# 6_DIG.net
KiCad netlist of a schematic drawn in Altium Designer
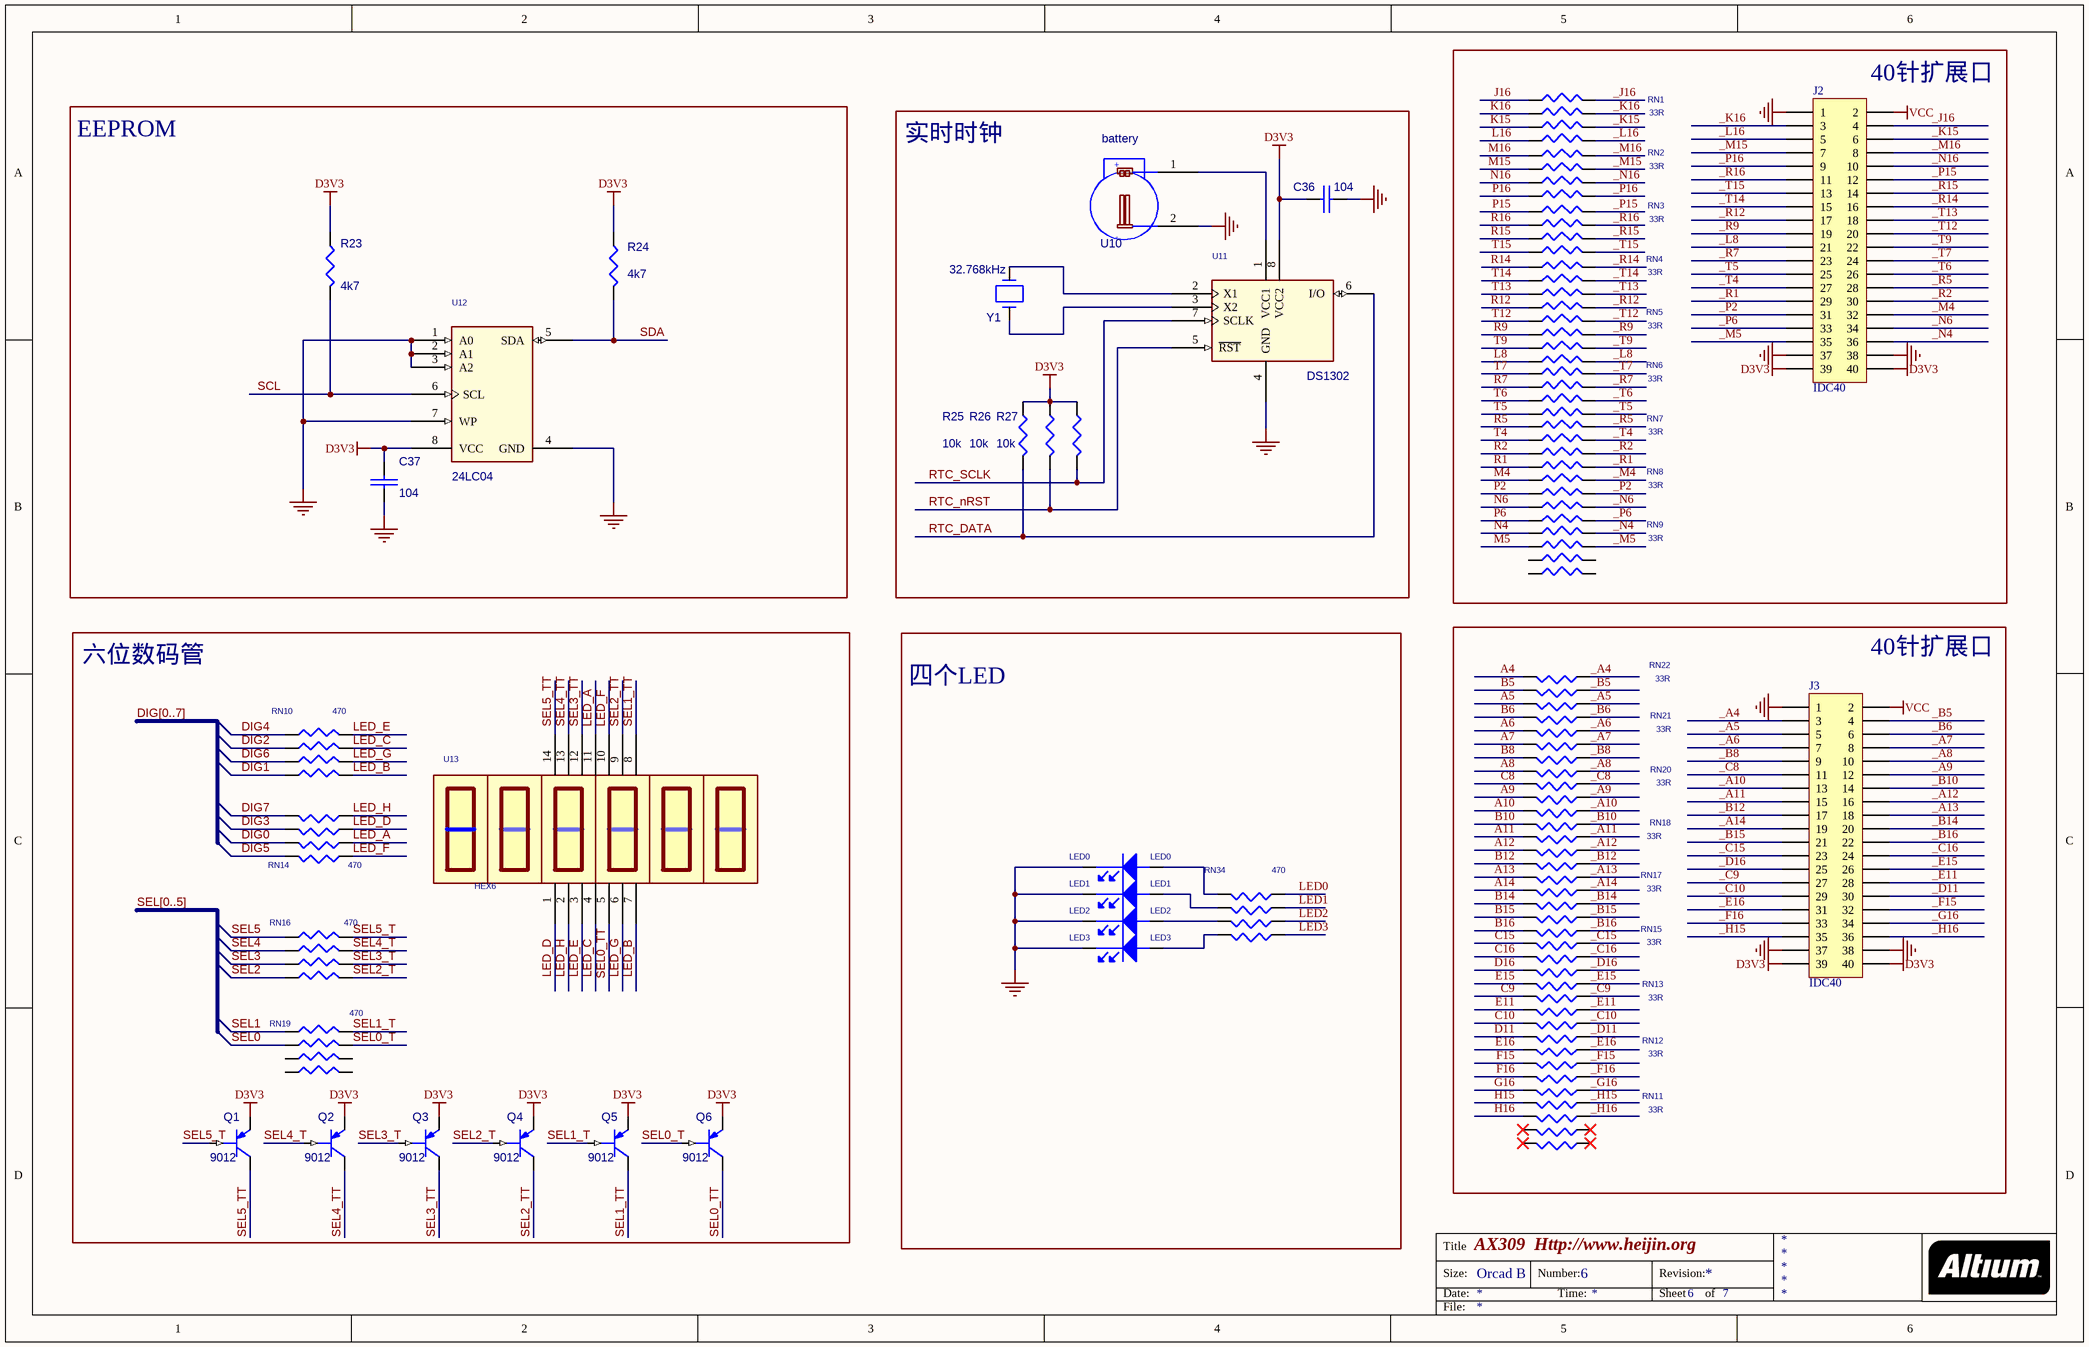
[diagram p0: 6_DIG.SchDoc]

(export (version "E")
  (design (tool "Eeschema 10.0.6"))
  (components
    (comp (ref "C36") (value "104") (footprint "0402") (libsource (lib "*") (part "C_Dup3")))
    (comp (ref "C37") (value "104") (footprint "0402") (libsource (lib "*") (part "C_Dup4")))
    (comp (ref "J2")
      (value "IDC40")
      (footprint "IDC-40J")
      (description "Header, 20-Pin, Dual row")
      (fields (field (name "PUBLISHER") "Altium Limited"))
      (libsource (lib "Miscellaneous Connectors") (part "MHDR2X20"))
    )
    (comp (ref "J3")
      (value "IDC40")
      (footprint "IDC-40J")
      (description "Header, 20-Pin, Dual row")
      (fields (field (name "PUBLISHER") "Altium Limited"))
      (libsource (lib "Miscellaneous Connectors") (part "MHDR2X20"))
    )
    (comp (ref "LED0") (value "LED0") (footprint "LEDSO") (libsource (lib "*") (part "LED_Dup1")))
    (comp (ref "LED1") (value "LED1") (footprint "LEDso") (libsource (lib "*") (part "LED_Dup1")))
    (comp (ref "LED2") (value "LED2") (footprint "LEDSO") (libsource (lib "*") (part "LED_Dup1")))
    (comp (ref "LED3") (value "LED3") (footprint "LEDSO") (libsource (lib "*") (part "LED_Dup1")))
    (comp (ref "Q1") (value "9012") (footprint "SOT23") (libsource (lib "*") (part "PNP")))
    (comp (ref "Q2") (value "9012") (footprint "SOT23") (libsource (lib "*") (part "PNP")))
    (comp (ref "Q3") (value "9012") (footprint "SOT23") (libsource (lib "*") (part "PNP")))
    (comp (ref "Q4") (value "9012") (footprint "SOT23") (libsource (lib "*") (part "PNP")))
    (comp (ref "Q5") (value "9012") (footprint "SOT23") (libsource (lib "*") (part "PNP")))
    (comp (ref "Q6") (value "9012") (footprint "SOT23") (libsource (lib "*") (part "PNP")))
    (comp (ref "R23") (value "4k7") (footprint "0603") (libsource (lib "*") (part "R_Dup6")))
    (comp (ref "R24") (value "4k7") (footprint "0603") (libsource (lib "*") (part "R_Dup6")))
    (comp (ref "R25") (value "10k") (footprint "0603") (libsource (lib "*") (part "R_Dup5")))
    (comp (ref "R26") (value "10k") (footprint "0603") (libsource (lib "*") (part "R_Dup5")))
    (comp (ref "R27") (value "10k") (footprint "0603") (libsource (lib "*") (part "R_Dup5")))
    (comp (ref "RN1") (value "33R") (footprint "RN-8P") (libsource (lib "*") (part "RN_Dup1")))
    (comp (ref "RN2") (value "33R") (footprint "RN-8P") (libsource (lib "*") (part "RN_Dup1")))
    (comp (ref "RN3") (value "33R") (footprint "RN-8P") (libsource (lib "*") (part "RN_Dup1")))
    (comp (ref "RN4") (value "33R") (footprint "RN-8P") (libsource (lib "*") (part "RN_Dup1")))
    (comp (ref "RN5") (value "33R") (footprint "RN-8P") (libsource (lib "*") (part "RN_Dup1")))
    (comp (ref "RN6") (value "33R") (footprint "RN-8P") (libsource (lib "*") (part "RN_Dup1")))
    (comp (ref "RN7") (value "33R") (footprint "RN-8P") (libsource (lib "*") (part "RN_Dup1")))
    (comp (ref "RN8") (value "33R") (footprint "RN-8P") (libsource (lib "*") (part "RN_Dup1")))
    (comp (ref "RN9") (value "33R") (footprint "RN-8P") (libsource (lib "*") (part "RN_Dup1")))
    (comp (ref "RN10") (value "470") (footprint "RN-8P") (libsource (lib "*") (part "RN")))
    (comp (ref "RN11") (value "33R") (footprint "RN-8P") (libsource (lib "*") (part "RN_Dup1")))
    (comp (ref "RN12") (value "33R") (footprint "RN-8P") (libsource (lib "*") (part "RN_Dup1")))
    (comp (ref "RN13") (value "33R") (footprint "RN-8P") (libsource (lib "*") (part "RN_Dup1")))
    (comp (ref "RN14") (value "470") (footprint "RN-8P") (libsource (lib "*") (part "RN")))
    (comp (ref "RN15") (value "33R") (footprint "RN-8P") (libsource (lib "*") (part "RN_Dup1")))
    (comp (ref "RN16") (value "470") (footprint "RN-8P") (libsource (lib "*") (part "RN")))
    (comp (ref "RN17") (value "33R") (footprint "RN-8P") (libsource (lib "*") (part "RN_Dup1")))
    (comp (ref "RN18") (value "33R") (footprint "RN-8P") (libsource (lib "*") (part "RN_Dup1")))
    (comp (ref "RN19") (value "470") (footprint "RN-8P") (libsource (lib "*") (part "RN")))
    (comp (ref "RN20") (value "33R") (footprint "RN-8P") (libsource (lib "*") (part "RN_Dup1")))
    (comp (ref "RN21") (value "33R") (footprint "RN-8P") (libsource (lib "*") (part "RN_Dup1")))
    (comp (ref "RN22") (value "33R") (footprint "RN-8P") (libsource (lib "*") (part "RN_Dup1")))
    (comp (ref "RN34") (value "470") (footprint "RN-8P") (libsource (lib "*") (part "RN")))
    (comp (ref "U10") (value "battery") (footprint "BATSO") (libsource (lib "*") (part "battery")))
    (comp (ref "U11")
      (value "DS1302")
      (fields (field (name "PART NUMBER") "TMP-13") (field (name "ICA_PARTNUM") "$$2098133$$DS1302S"))
      (libsource (lib "*") (part "DS1302_8SO"))
    )
    (comp (ref "U12") (value "24LC04") (libsource (lib "*") (part "24LC04B_0")))
    (comp (ref "U13") (value "HEX6") (libsource (lib "*") (part "HEX6")))
    (comp (ref "Y1") (value "32.768kHz") (libsource (lib "*") (part "ZTA")))
  )
  (nets
    (net (code "1") (name "/A4") (class "Default")
      (node (ref "RN22") (pin "5") (pinfunction "5_5") (pintype "passive"))
    )
    (net (code "2") (name "/A5") (class "Default")
      (node (ref "RN22") (pin "7") (pinfunction "7_7") (pintype "passive"))
    )
    (net (code "3") (name "/A6") (class "Default")
      (node (ref "RN21") (pin "5") (pinfunction "5_5") (pintype "passive"))
    )
    (net (code "4") (name "/A7") (class "Default")
      (node (ref "RN21") (pin "6") (pinfunction "6_6") (pintype "passive"))
    )
    (net (code "5") (name "/A8") (class "Default")
      (node (ref "RN21") (pin "8") (pinfunction "8_8") (pintype "passive"))
    )
    (net (code "6") (name "/A9") (class "Default")
      (node (ref "RN20") (pin "6") (pinfunction "6_6") (pintype "passive"))
    )
    (net (code "7") (name "/A10") (class "Default")
      (node (ref "RN20") (pin "7") (pinfunction "7_7") (pintype "passive"))
    )
    (net (code "8") (name "/A11") (class "Default")
      (node (ref "RN18") (pin "5") (pinfunction "5_5") (pintype "passive"))
    )
    (net (code "9") (name "/A12") (class "Default")
      (node (ref "RN18") (pin "6") (pinfunction "6_6") (pintype "passive"))
    )
    (net (code "10") (name "/A13") (class "Default")
      (node (ref "RN18") (pin "8") (pinfunction "8_8") (pintype "passive"))
    )
    (net (code "11") (name "/A14") (class "Default")
      (node (ref "RN17") (pin "5") (pinfunction "5_5") (pintype "passive"))
    )
    (net (code "12") (name "/B5") (class "Default")
      (node (ref "RN22") (pin "6") (pinfunction "6_6") (pintype "passive"))
    )
    (net (code "13") (name "/B6") (class "Default")
      (node (ref "RN22") (pin "8") (pinfunction "8_8") (pintype "passive"))
    )
    (net (code "14") (name "/B8") (class "Default")
      (node (ref "RN21") (pin "7") (pinfunction "7_7") (pintype "passive"))
    )
    (net (code "15") (name "/B10") (class "Default")
      (node (ref "RN20") (pin "8") (pinfunction "8_8") (pintype "passive"))
    )
    (net (code "16") (name "/B12") (class "Default")
      (node (ref "RN18") (pin "7") (pinfunction "7_7") (pintype "passive"))
    )
    (net (code "17") (name "/B14") (class "Default")
      (node (ref "RN17") (pin "6") (pinfunction "6_6") (pintype "passive"))
    )
    (net (code "18") (name "/B15") (class "Default")
      (node (ref "RN17") (pin "7") (pinfunction "7_7") (pintype "passive"))
    )
    (net (code "19") (name "/B16") (class "Default")
      (node (ref "RN17") (pin "8") (pinfunction "8_8") (pintype "passive"))
    )
    (net (code "20") (name "/C8") (class "Default")
      (node (ref "RN20") (pin "5") (pinfunction "5_5") (pintype "passive"))
    )
    (net (code "21") (name "/C9") (class "Default")
      (node (ref "RN13") (pin "5") (pinfunction "5_5") (pintype "passive"))
    )
    (net (code "22") (name "/C10") (class "Default")
      (node (ref "RN13") (pin "7") (pinfunction "7_7") (pintype "passive"))
    )
    (net (code "23") (name "/C15") (class "Default")
      (node (ref "RN15") (pin "5") (pinfunction "5_5") (pintype "passive"))
    )
    (net (code "24") (name "/C16") (class "Default")
      (node (ref "RN15") (pin "6") (pinfunction "6_6") (pintype "passive"))
    )
    (net (code "25") (name "/D11") (class "Default")
      (node (ref "RN13") (pin "8") (pinfunction "8_8") (pintype "passive"))
    )
    (net (code "26") (name "/D16") (class "Default")
      (node (ref "RN15") (pin "7") (pinfunction "7_7") (pintype "passive"))
    )
    (net (code "27") (name "/DIG0") (class "Default")
      (node (ref "RN14") (pin "7") (pinfunction "7_7") (pintype "passive"))
    )
    (net (code "28") (name "/DIG1") (class "Default")
      (node (ref "RN10") (pin "5") (pinfunction "5_5") (pintype "passive"))
    )
    (net (code "29") (name "/DIG2") (class "Default")
      (node (ref "RN10") (pin "7") (pinfunction "7_7") (pintype "passive"))
    )
    (net (code "30") (name "/DIG3") (class "Default")
      (node (ref "RN14") (pin "6") (pinfunction "6_6") (pintype "passive"))
    )
    (net (code "31") (name "/DIG4") (class "Default")
      (node (ref "RN10") (pin "8") (pinfunction "8_8") (pintype "passive"))
    )
    (net (code "32") (name "/DIG5") (class "Default")
      (node (ref "RN14") (pin "8") (pinfunction "8_8") (pintype "passive"))
    )
    (net (code "33") (name "/DIG6") (class "Default")
      (node (ref "RN10") (pin "6") (pinfunction "6_6") (pintype "passive"))
    )
    (net (code "34") (name "/DIG7") (class "Default")
      (node (ref "RN14") (pin "5") (pinfunction "5_5") (pintype "passive"))
    )
    (net (code "36") (name "/E11") (class "Default")
      (node (ref "RN13") (pin "6") (pinfunction "6_6") (pintype "passive"))
    )
    (net (code "37") (name "/E15") (class "Default")
      (node (ref "RN15") (pin "8") (pinfunction "8_8") (pintype "passive"))
    )
    (net (code "38") (name "/E16") (class "Default")
      (node (ref "RN12") (pin "5") (pinfunction "5_5") (pintype "passive"))
    )
    (net (code "39") (name "/F15") (class "Default")
      (node (ref "RN12") (pin "6") (pinfunction "6_6") (pintype "passive"))
    )
    (net (code "40") (name "/F16") (class "Default")
      (node (ref "RN12") (pin "7") (pinfunction "7_7") (pintype "passive"))
    )
    (net (code "41") (name "/G16") (class "Default")
      (node (ref "RN12") (pin "8") (pinfunction "8_8") (pintype "passive"))
    )
    (net (code "42") (name "/H15") (class "Default")
      (node (ref "RN11") (pin "5") (pinfunction "5_5") (pintype "passive"))
    )
    (net (code "43") (name "/H16") (class "Default")
      (node (ref "RN11") (pin "6") (pinfunction "6_6") (pintype "passive"))
    )
    (net (code "44") (name "/J16") (class "Default")
      (node (ref "RN1") (pin "1") (pinfunction "1_1") (pintype "passive"))
    )
    (net (code "45") (name "/K15") (class "Default")
      (node (ref "RN1") (pin "3") (pinfunction "3_3") (pintype "passive"))
    )
    (net (code "46") (name "/K16") (class "Default")
      (node (ref "RN1") (pin "2") (pinfunction "2_2") (pintype "passive"))
    )
    (net (code "47") (name "/L8") (class "Default")
      (node (ref "RN5") (pin "4") (pinfunction "4_4") (pintype "passive"))
    )
    (net (code "48") (name "/L16") (class "Default")
      (node (ref "RN1") (pin "4") (pinfunction "4_4") (pintype "passive"))
    )
    (net (code "49") (name "/LED0") (class "Default")
      (node (ref "RN34") (pin "4") (pinfunction "4_4") (pintype "passive"))
    )
    (net (code "50") (name "/LED1") (class "Default")
      (node (ref "RN34") (pin "3") (pinfunction "3_3") (pintype "passive"))
    )
    (net (code "51") (name "/LED2") (class "Default")
      (node (ref "RN34") (pin "2") (pinfunction "2_2") (pintype "passive"))
    )
    (net (code "52") (name "/LED3") (class "Default")
      (node (ref "RN34") (pin "1") (pinfunction "1_1") (pintype "passive"))
    )
    (net (code "53") (name "/LED_A") (class "Default")
      (node (ref "RN14") (pin "2") (pinfunction "2_2") (pintype "passive"))
      (node (ref "U13") (pin "11") (pinfunction "11_11") (pintype "passive"))
    )
    (net (code "54") (name "/LED_B") (class "Default")
      (node (ref "RN10") (pin "4") (pinfunction "4_4") (pintype "passive"))
      (node (ref "U13") (pin "7") (pinfunction "7_7") (pintype "passive"))
    )
    (net (code "55") (name "/LED_C") (class "Default")
      (node (ref "RN10") (pin "2") (pinfunction "2_2") (pintype "passive"))
      (node (ref "U13") (pin "4") (pinfunction "4_4") (pintype "passive"))
    )
    (net (code "56") (name "/LED_D") (class "Default")
      (node (ref "RN14") (pin "3") (pinfunction "3_3") (pintype "passive"))
      (node (ref "U13") (pin "1") (pinfunction "1_1") (pintype "passive"))
    )
    (net (code "57") (name "/LED_E") (class "Default")
      (node (ref "RN10") (pin "1") (pinfunction "1_1") (pintype "passive"))
      (node (ref "U13") (pin "3") (pinfunction "3_3") (pintype "passive"))
    )
    (net (code "58") (name "/LED_F") (class "Default")
      (node (ref "RN14") (pin "1") (pinfunction "1_1") (pintype "passive"))
      (node (ref "U13") (pin "10") (pinfunction "10_10") (pintype "passive"))
    )
    (net (code "59") (name "/LED_G") (class "Default")
      (node (ref "RN10") (pin "3") (pinfunction "3_3") (pintype "passive"))
      (node (ref "U13") (pin "6") (pinfunction "6_6") (pintype "passive"))
    )
    (net (code "60") (name "/LED_H") (class "Default")
      (node (ref "RN14") (pin "4") (pinfunction "4_4") (pintype "passive"))
      (node (ref "U13") (pin "2") (pinfunction "2_2") (pintype "passive"))
    )
    (net (code "61") (name "/M4") (class "Default")
      (node (ref "RN8") (pin "1") (pinfunction "1_1") (pintype "passive"))
    )
    (net (code "62") (name "/M5") (class "Default")
      (node (ref "RN9") (pin "2") (pinfunction "2_2") (pintype "passive"))
    )
    (net (code "63") (name "/M15") (class "Default")
      (node (ref "RN2") (pin "2") (pinfunction "2_2") (pintype "passive"))
    )
    (net (code "64") (name "/M16") (class "Default")
      (node (ref "RN2") (pin "1") (pinfunction "1_1") (pintype "passive"))
    )
    (net (code "65") (name "/N4") (class "Default")
      (node (ref "RN9") (pin "1") (pinfunction "1_1") (pintype "passive"))
    )
    (net (code "66") (name "/N6") (class "Default")
      (node (ref "RN8") (pin "3") (pinfunction "3_3") (pintype "passive"))
    )
    (net (code "67") (name "/N16") (class "Default")
      (node (ref "RN2") (pin "3") (pinfunction "3_3") (pintype "passive"))
    )
    (net (code "68") (name "/P2") (class "Default")
      (node (ref "RN8") (pin "2") (pinfunction "2_2") (pintype "passive"))
    )
    (net (code "69") (name "/P6") (class "Default")
      (node (ref "RN8") (pin "4") (pinfunction "4_4") (pintype "passive"))
    )
    (net (code "70") (name "/P15") (class "Default")
      (node (ref "RN3") (pin "1") (pinfunction "1_1") (pintype "passive"))
    )
    (net (code "71") (name "/P16") (class "Default")
      (node (ref "RN2") (pin "4") (pinfunction "4_4") (pintype "passive"))
    )
    (net (code "72") (name "/R1") (class "Default")
      (node (ref "RN7") (pin "4") (pinfunction "4_4") (pintype "passive"))
    )
    (net (code "73") (name "/R2") (class "Default")
      (node (ref "RN7") (pin "3") (pinfunction "3_3") (pintype "passive"))
    )
    (net (code "74") (name "/R5") (class "Default")
      (node (ref "RN7") (pin "1") (pinfunction "1_1") (pintype "passive"))
    )
    (net (code "75") (name "/R7") (class "Default")
      (node (ref "RN6") (pin "2") (pinfunction "2_2") (pintype "passive"))
    )
    (net (code "76") (name "/R9") (class "Default")
      (node (ref "RN5") (pin "2") (pinfunction "2_2") (pintype "passive"))
    )
    (net (code "77") (name "/R12") (class "Default")
      (node (ref "RN4") (pin "4") (pinfunction "4_4") (pintype "passive"))
    )
    (net (code "78") (name "/R14") (class "Default")
      (node (ref "RN4") (pin "1") (pinfunction "1_1") (pintype "passive"))
    )
    (net (code "79") (name "/R15") (class "Default")
      (node (ref "RN3") (pin "3") (pinfunction "3_3") (pintype "passive"))
    )
    (net (code "80") (name "/R16") (class "Default")
      (node (ref "RN3") (pin "2") (pinfunction "2_2") (pintype "passive"))
    )
    (net (code "81") (name "/RTC_DATA") (class "Default")
      (node (ref "R25") (pin "2") (pinfunction "2_2") (pintype "passive"))
      (node (ref "U11") (pin "6") (pinfunction "I/O_6") (pintype "bidirectional"))
    )
    (net (code "82") (name "/RTC_SCLK") (class "Default")
      (node (ref "R27") (pin "2") (pinfunction "2_2") (pintype "passive"))
      (node (ref "U11") (pin "7") (pinfunction "SCLK_7") (pintype "input"))
    )
    (net (code "83") (name "/RTC_nRST") (class "Default")
      (node (ref "R26") (pin "2") (pinfunction "2_2") (pintype "passive"))
      (node (ref "U11") (pin "5") (pinfunction "~{RST}_5") (pintype "input"))
    )
    (net (code "84") (name "/SCL") (class "Default")
      (node (ref "R23") (pin "2") (pinfunction "2_2") (pintype "passive"))
      (node (ref "U12") (pin "6") (pinfunction "SCL_6") (pintype "input"))
    )
    (net (code "85") (name "/SDA") (class "Default")
      (node (ref "R24") (pin "2") (pinfunction "2_2") (pintype "passive"))
      (node (ref "U12") (pin "5") (pinfunction "SDA_5") (pintype "bidirectional"))
    )
    (net (code "86") (name "/SEL0") (class "Default")
      (node (ref "RN19") (pin "7") (pinfunction "7_7") (pintype "passive"))
    )
    (net (code "87") (name "/SEL0_T") (class "Default")
      (node (ref "Q6") (pin "1") (pinfunction "BASE_1") (pintype "input"))
      (node (ref "RN19") (pin "2") (pinfunction "2_2") (pintype "passive"))
    )
    (net (code "88") (name "/SEL0_TT") (class "Default")
      (node (ref "Q6") (pin "3") (pinfunction "COLLECTOR_3") (pintype "passive"))
      (node (ref "U13") (pin "5") (pinfunction "5_5") (pintype "passive"))
    )
    (net (code "89") (name "/SEL1") (class "Default")
      (node (ref "RN19") (pin "8") (pinfunction "8_8") (pintype "passive"))
    )
    (net (code "90") (name "/SEL1_T") (class "Default")
      (node (ref "Q5") (pin "1") (pinfunction "BASE_1") (pintype "input"))
      (node (ref "RN19") (pin "1") (pinfunction "1_1") (pintype "passive"))
    )
    (net (code "91") (name "/SEL1_TT") (class "Default")
      (node (ref "Q5") (pin "3") (pinfunction "COLLECTOR_3") (pintype "passive"))
      (node (ref "U13") (pin "8") (pinfunction "8_8") (pintype "passive"))
    )
    (net (code "92") (name "/SEL2") (class "Default")
      (node (ref "RN16") (pin "5") (pinfunction "5_5") (pintype "passive"))
    )
    (net (code "93") (name "/SEL2_T") (class "Default")
      (node (ref "Q4") (pin "1") (pinfunction "BASE_1") (pintype "input"))
      (node (ref "RN16") (pin "4") (pinfunction "4_4") (pintype "passive"))
    )
    (net (code "94") (name "/SEL2_TT") (class "Default")
      (node (ref "Q4") (pin "3") (pinfunction "COLLECTOR_3") (pintype "passive"))
      (node (ref "U13") (pin "9") (pinfunction "9_9") (pintype "passive"))
    )
    (net (code "95") (name "/SEL3") (class "Default")
      (node (ref "RN16") (pin "6") (pinfunction "6_6") (pintype "passive"))
    )
    (net (code "96") (name "/SEL3_T") (class "Default")
      (node (ref "Q3") (pin "1") (pinfunction "BASE_1") (pintype "input"))
      (node (ref "RN16") (pin "3") (pinfunction "3_3") (pintype "passive"))
    )
    (net (code "97") (name "/SEL3_TT") (class "Default")
      (node (ref "Q3") (pin "3") (pinfunction "COLLECTOR_3") (pintype "passive"))
      (node (ref "U13") (pin "12") (pinfunction "12_12") (pintype "passive"))
    )
    (net (code "98") (name "/SEL4") (class "Default")
      (node (ref "RN16") (pin "7") (pinfunction "7_7") (pintype "passive"))
    )
    (net (code "99") (name "/SEL4_T") (class "Default")
      (node (ref "Q2") (pin "1") (pinfunction "BASE_1") (pintype "input"))
      (node (ref "RN16") (pin "2") (pinfunction "2_2") (pintype "passive"))
    )
    (net (code "100") (name "/SEL4_TT") (class "Default")
      (node (ref "Q2") (pin "3") (pinfunction "COLLECTOR_3") (pintype "passive"))
      (node (ref "U13") (pin "13") (pinfunction "13_13") (pintype "passive"))
    )
    (net (code "101") (name "/SEL5") (class "Default")
      (node (ref "RN16") (pin "8") (pinfunction "8_8") (pintype "passive"))
    )
    (net (code "102") (name "/SEL5_T") (class "Default")
      (node (ref "Q1") (pin "1") (pinfunction "BASE_1") (pintype "input"))
      (node (ref "RN16") (pin "1") (pinfunction "1_1") (pintype "passive"))
    )
    (net (code "103") (name "/SEL5_TT") (class "Default")
      (node (ref "Q1") (pin "3") (pinfunction "COLLECTOR_3") (pintype "passive"))
      (node (ref "U13") (pin "14") (pinfunction "14_14") (pintype "passive"))
    )
    (net (code "105") (name "/T4") (class "Default")
      (node (ref "RN7") (pin "2") (pinfunction "2_2") (pintype "passive"))
    )
    (net (code "106") (name "/T5") (class "Default")
      (node (ref "RN6") (pin "4") (pinfunction "4_4") (pintype "passive"))
    )
    (net (code "107") (name "/T6") (class "Default")
      (node (ref "RN6") (pin "3") (pinfunction "3_3") (pintype "passive"))
    )
    (net (code "108") (name "/T7") (class "Default")
      (node (ref "RN6") (pin "1") (pinfunction "1_1") (pintype "passive"))
    )
    (net (code "109") (name "/T9") (class "Default")
      (node (ref "RN5") (pin "3") (pinfunction "3_3") (pintype "passive"))
    )
    (net (code "110") (name "/T12") (class "Default")
      (node (ref "RN5") (pin "1") (pinfunction "1_1") (pintype "passive"))
    )
    (net (code "111") (name "/T13") (class "Default")
      (node (ref "RN4") (pin "3") (pinfunction "3_3") (pintype "passive"))
    )
    (net (code "112") (name "/T14") (class "Default")
      (node (ref "RN4") (pin "2") (pinfunction "2_2") (pintype "passive"))
    )
    (net (code "113") (name "/T15") (class "Default")
      (node (ref "RN3") (pin "4") (pinfunction "4_4") (pintype "passive"))
    )
    (net (code "114") (name "/_A4") (class "Default")
      (node (ref "J3") (pin "3") (pinfunction "3_3") (pintype "passive"))
      (node (ref "RN22") (pin "4") (pinfunction "4_4") (pintype "passive"))
    )
    (net (code "115") (name "/_A5") (class "Default")
      (node (ref "J3") (pin "5") (pinfunction "5_5") (pintype "passive"))
      (node (ref "RN22") (pin "2") (pinfunction "2_2") (pintype "passive"))
    )
    (net (code "116") (name "/_A6") (class "Default")
      (node (ref "J3") (pin "7") (pinfunction "7_7") (pintype "passive"))
      (node (ref "RN21") (pin "4") (pinfunction "4_4") (pintype "passive"))
    )
    (net (code "117") (name "/_A7") (class "Default")
      (node (ref "J3") (pin "8") (pinfunction "8_8") (pintype "passive"))
      (node (ref "RN21") (pin "3") (pinfunction "3_3") (pintype "passive"))
    )
    (net (code "118") (name "/_A8") (class "Default")
      (node (ref "J3") (pin "10") (pinfunction "10_10") (pintype "passive"))
      (node (ref "RN21") (pin "1") (pinfunction "1_1") (pintype "passive"))
    )
    (net (code "119") (name "/_A9") (class "Default")
      (node (ref "J3") (pin "12") (pinfunction "12_12") (pintype "passive"))
      (node (ref "RN20") (pin "3") (pinfunction "3_3") (pintype "passive"))
    )
    (net (code "120") (name "/_A10") (class "Default")
      (node (ref "J3") (pin "13") (pinfunction "13_13") (pintype "passive"))
      (node (ref "RN20") (pin "2") (pinfunction "2_2") (pintype "passive"))
    )
    (net (code "121") (name "/_A11") (class "Default")
      (node (ref "J3") (pin "15") (pinfunction "15_15") (pintype "passive"))
      (node (ref "RN18") (pin "4") (pinfunction "4_4") (pintype "passive"))
    )
    (net (code "122") (name "/_A12") (class "Default")
      (node (ref "J3") (pin "16") (pinfunction "16_16") (pintype "passive"))
      (node (ref "RN18") (pin "3") (pinfunction "3_3") (pintype "passive"))
    )
    (net (code "123") (name "/_A13") (class "Default")
      (node (ref "J3") (pin "18") (pinfunction "18_18") (pintype "passive"))
      (node (ref "RN18") (pin "1") (pinfunction "1_1") (pintype "passive"))
    )
    (net (code "124") (name "/_A14") (class "Default")
      (node (ref "J3") (pin "19") (pinfunction "19_19") (pintype "passive"))
      (node (ref "RN17") (pin "4") (pinfunction "4_4") (pintype "passive"))
    )
    (net (code "125") (name "/_B5") (class "Default")
      (node (ref "J3") (pin "4") (pinfunction "4_4") (pintype "passive"))
      (node (ref "RN22") (pin "3") (pinfunction "3_3") (pintype "passive"))
    )
    (net (code "126") (name "/_B6") (class "Default")
      (node (ref "J3") (pin "6") (pinfunction "6_6") (pintype "passive"))
      (node (ref "RN22") (pin "1") (pinfunction "1_1") (pintype "passive"))
    )
    (net (code "127") (name "/_B8") (class "Default")
      (node (ref "J3") (pin "9") (pinfunction "9_9") (pintype "passive"))
      (node (ref "RN21") (pin "2") (pinfunction "2_2") (pintype "passive"))
    )
    (net (code "128") (name "/_B10") (class "Default")
      (node (ref "J3") (pin "14") (pinfunction "14_14") (pintype "passive"))
      (node (ref "RN20") (pin "1") (pinfunction "1_1") (pintype "passive"))
    )
    (net (code "129") (name "/_B12") (class "Default")
      (node (ref "J3") (pin "17") (pinfunction "17_17") (pintype "passive"))
      (node (ref "RN18") (pin "2") (pinfunction "2_2") (pintype "passive"))
    )
    (net (code "130") (name "/_B14") (class "Default")
      (node (ref "J3") (pin "20") (pinfunction "20_20") (pintype "passive"))
      (node (ref "RN17") (pin "3") (pinfunction "3_3") (pintype "passive"))
    )
    (net (code "131") (name "/_B15") (class "Default")
      (node (ref "J3") (pin "21") (pinfunction "21_21") (pintype "passive"))
      (node (ref "RN17") (pin "2") (pinfunction "2_2") (pintype "passive"))
    )
    (net (code "132") (name "/_B16") (class "Default")
      (node (ref "J3") (pin "22") (pinfunction "22_22") (pintype "passive"))
      (node (ref "RN17") (pin "1") (pinfunction "1_1") (pintype "passive"))
    )
    (net (code "133") (name "/_C8") (class "Default")
      (node (ref "J3") (pin "11") (pinfunction "11_11") (pintype "passive"))
      (node (ref "RN20") (pin "4") (pinfunction "4_4") (pintype "passive"))
    )
    (net (code "134") (name "/_C9") (class "Default")
      (node (ref "J3") (pin "27") (pinfunction "27_27") (pintype "passive"))
      (node (ref "RN13") (pin "4") (pinfunction "4_4") (pintype "passive"))
    )
    (net (code "135") (name "/_C10") (class "Default")
      (node (ref "J3") (pin "29") (pinfunction "29_29") (pintype "passive"))
      (node (ref "RN13") (pin "2") (pinfunction "2_2") (pintype "passive"))
    )
    (net (code "136") (name "/_C15") (class "Default")
      (node (ref "J3") (pin "23") (pinfunction "23_23") (pintype "passive"))
      (node (ref "RN15") (pin "4") (pinfunction "4_4") (pintype "passive"))
    )
    (net (code "137") (name "/_C16") (class "Default")
      (node (ref "J3") (pin "24") (pinfunction "24_24") (pintype "passive"))
      (node (ref "RN15") (pin "3") (pinfunction "3_3") (pintype "passive"))
    )
    (net (code "138") (name "/_D11") (class "Default")
      (node (ref "J3") (pin "30") (pinfunction "30_30") (pintype "passive"))
      (node (ref "RN13") (pin "1") (pinfunction "1_1") (pintype "passive"))
    )
    (net (code "139") (name "/_D16") (class "Default")
      (node (ref "J3") (pin "25") (pinfunction "25_25") (pintype "passive"))
      (node (ref "RN15") (pin "2") (pinfunction "2_2") (pintype "passive"))
    )
    (net (code "140") (name "/_E11") (class "Default")
      (node (ref "J3") (pin "28") (pinfunction "28_28") (pintype "passive"))
      (node (ref "RN13") (pin "3") (pinfunction "3_3") (pintype "passive"))
    )
    (net (code "141") (name "/_E15") (class "Default")
      (node (ref "J3") (pin "26") (pinfunction "26_26") (pintype "passive"))
      (node (ref "RN15") (pin "1") (pinfunction "1_1") (pintype "passive"))
    )
    (net (code "142") (name "/_E16") (class "Default")
      (node (ref "J3") (pin "31") (pinfunction "31_31") (pintype "passive"))
      (node (ref "RN12") (pin "4") (pinfunction "4_4") (pintype "passive"))
    )
    (net (code "143") (name "/_F15") (class "Default")
      (node (ref "J3") (pin "32") (pinfunction "32_32") (pintype "passive"))
      (node (ref "RN12") (pin "3") (pinfunction "3_3") (pintype "passive"))
    )
    (net (code "144") (name "/_F16") (class "Default")
      (node (ref "J3") (pin "33") (pinfunction "33_33") (pintype "passive"))
      (node (ref "RN12") (pin "2") (pinfunction "2_2") (pintype "passive"))
    )
    (net (code "145") (name "/_G16") (class "Default")
      (node (ref "J3") (pin "34") (pinfunction "34_34") (pintype "passive"))
      (node (ref "RN12") (pin "1") (pinfunction "1_1") (pintype "passive"))
    )
    (net (code "146") (name "/_H15") (class "Default")
      (node (ref "J3") (pin "35") (pinfunction "35_35") (pintype "passive"))
      (node (ref "RN11") (pin "4") (pinfunction "4_4") (pintype "passive"))
    )
    (net (code "147") (name "/_H16") (class "Default")
      (node (ref "J3") (pin "36") (pinfunction "36_36") (pintype "passive"))
      (node (ref "RN11") (pin "3") (pinfunction "3_3") (pintype "passive"))
    )
    (net (code "148") (name "/_J16") (class "Default")
      (node (ref "J2") (pin "4") (pinfunction "4_4") (pintype "passive"))
      (node (ref "RN1") (pin "8") (pinfunction "8_8") (pintype "passive"))
    )
    (net (code "149") (name "/_K15") (class "Default")
      (node (ref "J2") (pin "6") (pinfunction "6_6") (pintype "passive"))
      (node (ref "RN1") (pin "6") (pinfunction "6_6") (pintype "passive"))
    )
    (net (code "150") (name "/_K16") (class "Default")
      (node (ref "J2") (pin "3") (pinfunction "3_3") (pintype "passive"))
      (node (ref "RN1") (pin "7") (pinfunction "7_7") (pintype "passive"))
    )
    (net (code "151") (name "/_L8") (class "Default")
      (node (ref "J2") (pin "21") (pinfunction "21_21") (pintype "passive"))
      (node (ref "RN5") (pin "5") (pinfunction "5_5") (pintype "passive"))
    )
    (net (code "152") (name "/_L16") (class "Default")
      (node (ref "J2") (pin "5") (pinfunction "5_5") (pintype "passive"))
      (node (ref "RN1") (pin "5") (pinfunction "5_5") (pintype "passive"))
    )
    (net (code "153") (name "/_M4") (class "Default")
      (node (ref "J2") (pin "32") (pinfunction "32_32") (pintype "passive"))
      (node (ref "RN8") (pin "8") (pinfunction "8_8") (pintype "passive"))
    )
    (net (code "154") (name "/_M5") (class "Default")
      (node (ref "J2") (pin "35") (pinfunction "35_35") (pintype "passive"))
      (node (ref "RN9") (pin "7") (pinfunction "7_7") (pintype "passive"))
    )
    (net (code "155") (name "/_M15") (class "Default")
      (node (ref "J2") (pin "7") (pinfunction "7_7") (pintype "passive"))
      (node (ref "RN2") (pin "7") (pinfunction "7_7") (pintype "passive"))
    )
    (net (code "156") (name "/_M16") (class "Default")
      (node (ref "J2") (pin "8") (pinfunction "8_8") (pintype "passive"))
      (node (ref "RN2") (pin "8") (pinfunction "8_8") (pintype "passive"))
    )
    (net (code "157") (name "/_N4") (class "Default")
      (node (ref "J2") (pin "36") (pinfunction "36_36") (pintype "passive"))
      (node (ref "RN9") (pin "8") (pinfunction "8_8") (pintype "passive"))
    )
    (net (code "158") (name "/_N6") (class "Default")
      (node (ref "J2") (pin "34") (pinfunction "34_34") (pintype "passive"))
      (node (ref "RN8") (pin "6") (pinfunction "6_6") (pintype "passive"))
    )
    (net (code "159") (name "/_N16") (class "Default")
      (node (ref "J2") (pin "10") (pinfunction "10_10") (pintype "passive"))
      (node (ref "RN2") (pin "6") (pinfunction "6_6") (pintype "passive"))
    )
    (net (code "160") (name "/_P2") (class "Default")
      (node (ref "J2") (pin "31") (pinfunction "31_31") (pintype "passive"))
      (node (ref "RN8") (pin "7") (pinfunction "7_7") (pintype "passive"))
    )
    (net (code "161") (name "/_P6") (class "Default")
      (node (ref "J2") (pin "33") (pinfunction "33_33") (pintype "passive"))
      (node (ref "RN8") (pin "5") (pinfunction "5_5") (pintype "passive"))
    )
    (net (code "162") (name "/_P15") (class "Default")
      (node (ref "J2") (pin "12") (pinfunction "12_12") (pintype "passive"))
      (node (ref "RN3") (pin "8") (pinfunction "8_8") (pintype "passive"))
    )
    (net (code "163") (name "/_P16") (class "Default")
      (node (ref "J2") (pin "9") (pinfunction "9_9") (pintype "passive"))
      (node (ref "RN2") (pin "5") (pinfunction "5_5") (pintype "passive"))
    )
    (net (code "164") (name "/_R1") (class "Default")
      (node (ref "J2") (pin "29") (pinfunction "29_29") (pintype "passive"))
      (node (ref "RN7") (pin "5") (pinfunction "5_5") (pintype "passive"))
    )
    (net (code "165") (name "/_R2") (class "Default")
      (node (ref "J2") (pin "30") (pinfunction "30_30") (pintype "passive"))
      (node (ref "RN7") (pin "6") (pinfunction "6_6") (pintype "passive"))
    )
    (net (code "166") (name "/_R5") (class "Default")
      (node (ref "J2") (pin "28") (pinfunction "28_28") (pintype "passive"))
      (node (ref "RN7") (pin "8") (pinfunction "8_8") (pintype "passive"))
    )
    (net (code "167") (name "/_R7") (class "Default")
      (node (ref "J2") (pin "23") (pinfunction "23_23") (pintype "passive"))
      (node (ref "RN6") (pin "7") (pinfunction "7_7") (pintype "passive"))
    )
    (net (code "168") (name "/_R9") (class "Default")
      (node (ref "J2") (pin "19") (pinfunction "19_19") (pintype "passive"))
      (node (ref "RN5") (pin "7") (pinfunction "7_7") (pintype "passive"))
    )
    (net (code "169") (name "/_R12") (class "Default")
      (node (ref "J2") (pin "17") (pinfunction "17_17") (pintype "passive"))
      (node (ref "RN4") (pin "5") (pinfunction "5_5") (pintype "passive"))
    )
    (net (code "170") (name "/_R14") (class "Default")
      (node (ref "J2") (pin "16") (pinfunction "16_16") (pintype "passive"))
      (node (ref "RN4") (pin "8") (pinfunction "8_8") (pintype "passive"))
    )
    (net (code "171") (name "/_R15") (class "Default")
      (node (ref "J2") (pin "14") (pinfunction "14_14") (pintype "passive"))
      (node (ref "RN3") (pin "6") (pinfunction "6_6") (pintype "passive"))
    )
    (net (code "172") (name "/_R16") (class "Default")
      (node (ref "J2") (pin "11") (pinfunction "11_11") (pintype "passive"))
      (node (ref "RN3") (pin "7") (pinfunction "7_7") (pintype "passive"))
    )
    (net (code "173") (name "/_T4") (class "Default")
      (node (ref "J2") (pin "27") (pinfunction "27_27") (pintype "passive"))
      (node (ref "RN7") (pin "7") (pinfunction "7_7") (pintype "passive"))
    )
    (net (code "174") (name "/_T5") (class "Default")
      (node (ref "J2") (pin "25") (pinfunction "25_25") (pintype "passive"))
      (node (ref "RN6") (pin "5") (pinfunction "5_5") (pintype "passive"))
    )
    (net (code "175") (name "/_T6") (class "Default")
      (node (ref "J2") (pin "26") (pinfunction "26_26") (pintype "passive"))
      (node (ref "RN6") (pin "6") (pinfunction "6_6") (pintype "passive"))
    )
    (net (code "176") (name "/_T7") (class "Default")
      (node (ref "J2") (pin "24") (pinfunction "24_24") (pintype "passive"))
      (node (ref "RN6") (pin "8") (pinfunction "8_8") (pintype "passive"))
    )
    (net (code "177") (name "/_T9") (class "Default")
      (node (ref "J2") (pin "22") (pinfunction "22_22") (pintype "passive"))
      (node (ref "RN5") (pin "6") (pinfunction "6_6") (pintype "passive"))
    )
    (net (code "178") (name "/_T12") (class "Default")
      (node (ref "J2") (pin "20") (pinfunction "20_20") (pintype "passive"))
      (node (ref "RN5") (pin "8") (pinfunction "8_8") (pintype "passive"))
    )
    (net (code "179") (name "/_T13") (class "Default")
      (node (ref "J2") (pin "18") (pinfunction "18_18") (pintype "passive"))
      (node (ref "RN4") (pin "6") (pinfunction "6_6") (pintype "passive"))
    )
    (net (code "180") (name "/_T14") (class "Default")
      (node (ref "J2") (pin "15") (pinfunction "15_15") (pintype "passive"))
      (node (ref "RN4") (pin "7") (pinfunction "7_7") (pintype "passive"))
    )
    (net (code "181") (name "/_T15") (class "Default")
      (node (ref "J2") (pin "13") (pinfunction "13_13") (pintype "passive"))
      (node (ref "RN3") (pin "5") (pinfunction "5_5") (pintype "passive"))
    )
    (net (code "182") (name "D3V3") (class "Default")
      (node (ref "C36") (pin "1") (pinfunction "1_1") (pintype "passive"))
      (node (ref "C37") (pin "1") (pinfunction "1_1") (pintype "passive"))
      (node (ref "J2") (pin "39") (pinfunction "39_39") (pintype "passive"))
      (node (ref "J2") (pin "40") (pinfunction "40_40") (pintype "passive"))
      (node (ref "J3") (pin "39") (pinfunction "39_39") (pintype "passive"))
      (node (ref "J3") (pin "40") (pinfunction "40_40") (pintype "passive"))
      (node (ref "Q1") (pin "2") (pinfunction "EMITTER_2") (pintype "passive"))
      (node (ref "Q2") (pin "2") (pinfunction "EMITTER_2") (pintype "passive"))
      (node (ref "Q3") (pin "2") (pinfunction "EMITTER_2") (pintype "passive"))
      (node (ref "Q4") (pin "2") (pinfunction "EMITTER_2") (pintype "passive"))
      (node (ref "Q5") (pin "2") (pinfunction "EMITTER_2") (pintype "passive"))
      (node (ref "Q6") (pin "2") (pinfunction "EMITTER_2") (pintype "passive"))
      (node (ref "R23") (pin "1") (pinfunction "1_1") (pintype "passive"))
      (node (ref "R24") (pin "1") (pinfunction "1_1") (pintype "passive"))
      (node (ref "R25") (pin "1") (pinfunction "1_1") (pintype "passive"))
      (node (ref "R26") (pin "1") (pinfunction "1_1") (pintype "passive"))
      (node (ref "R27") (pin "1") (pinfunction "1_1") (pintype "passive"))
      (node (ref "U11") (pin "8") (pinfunction "VCC2_8") (pintype "power_in"))
      (node (ref "U12") (pin "8") (pinfunction "VCC_8") (pintype "power_in"))
    )
    (net (code "183") (name "GND") (class "Default")
      (node (ref "C36") (pin "2") (pinfunction "2_2") (pintype "passive"))
      (node (ref "C37") (pin "2") (pinfunction "2_2") (pintype "passive"))
      (node (ref "J2") (pin "1") (pinfunction "1_1") (pintype "passive"))
      (node (ref "J2") (pin "37") (pinfunction "37_37") (pintype "passive"))
      (node (ref "J2") (pin "38") (pinfunction "38_38") (pintype "passive"))
      (node (ref "J3") (pin "1") (pinfunction "1_1") (pintype "passive"))
      (node (ref "J3") (pin "37") (pinfunction "37_37") (pintype "passive"))
      (node (ref "J3") (pin "38") (pinfunction "38_38") (pintype "passive"))
      (node (ref "LED0") (pin "2") (pinfunction "CATHODE_2") (pintype "passive"))
      (node (ref "LED1") (pin "2") (pinfunction "CATHODE_2") (pintype "passive"))
      (node (ref "LED2") (pin "2") (pinfunction "CATHODE_2") (pintype "passive"))
      (node (ref "LED3") (pin "2") (pinfunction "CATHODE_2") (pintype "passive"))
      (node (ref "U10") (pin "2") (pinfunction "GND_2") (pintype "passive"))
      (node (ref "U11") (pin "4") (pinfunction "GND_4") (pintype "power_in"))
      (node (ref "U12") (pin "1") (pinfunction "A0_1") (pintype "input"))
      (node (ref "U12") (pin "2") (pinfunction "A1_2") (pintype "input"))
      (node (ref "U12") (pin "3") (pinfunction "A2_3") (pintype "input"))
      (node (ref "U12") (pin "4") (pinfunction "GND_4") (pintype "power_in"))
      (node (ref "U12") (pin "7") (pinfunction "WP_7") (pintype "input"))
    )
    (net (code "184") (name "Net-(LED0-ANODE)") (class "Default")
      (node (ref "LED0") (pin "1") (pinfunction "ANODE_1") (pintype "passive"))
      (node (ref "RN34") (pin "5") (pinfunction "5_5") (pintype "passive"))
    )
    (net (code "185") (name "Net-(LED1-ANODE)") (class "Default")
      (node (ref "LED1") (pin "1") (pinfunction "ANODE_1") (pintype "passive"))
      (node (ref "RN34") (pin "6") (pinfunction "6_6") (pintype "passive"))
    )
    (net (code "186") (name "Net-(LED2-ANODE)") (class "Default")
      (node (ref "LED2") (pin "1") (pinfunction "ANODE_1") (pintype "passive"))
      (node (ref "RN34") (pin "7") (pinfunction "7_7") (pintype "passive"))
    )
    (net (code "187") (name "Net-(LED3-ANODE)") (class "Default")
      (node (ref "LED3") (pin "1") (pinfunction "ANODE_1") (pintype "passive"))
      (node (ref "RN34") (pin "8") (pinfunction "8_8") (pintype "passive"))
    )
    (net (code "188") (name "Net-(U10-VBAT)") (class "Default")
      (node (ref "U10") (pin "1") (pinfunction "VBAT_1") (pintype "passive"))
      (node (ref "U11") (pin "1") (pinfunction "VCC1_1") (pintype "power_in"))
    )
    (net (code "189") (name "Net-(U11-X1)") (class "Default")
      (node (ref "U11") (pin "2") (pinfunction "X1_2") (pintype "passive"))
      (node (ref "Y1") (pin "1") (pinfunction "1_1") (pintype "passive"))
    )
    (net (code "190") (name "Net-(U11-X2)") (class "Default")
      (node (ref "U11") (pin "3") (pinfunction "X2_3") (pintype "passive"))
      (node (ref "Y1") (pin "2") (pinfunction "2_2") (pintype "passive"))
    )
    (net (code "191") (name "VCC") (class "Default")
      (node (ref "J2") (pin "2") (pinfunction "2_2") (pintype "passive"))
      (node (ref "J3") (pin "2") (pinfunction "2_2") (pintype "passive"))
    )
    (net (code "192") (name "unconnected-(RN9-Pad3)") (class "Default")
      (node (ref "RN9") (pin "3") (pinfunction "3_3") (pintype "passive"))
    )
    (net (code "193") (name "unconnected-(RN9-Pad4)") (class "Default")
      (node (ref "RN9") (pin "4") (pinfunction "4_4") (pintype "passive"))
    )
    (net (code "194") (name "unconnected-(RN9-Pad5)") (class "Default")
      (node (ref "RN9") (pin "5") (pinfunction "5_5") (pintype "passive"))
    )
    (net (code "195") (name "unconnected-(RN9-Pad6)") (class "Default")
      (node (ref "RN9") (pin "6") (pinfunction "6_6") (pintype "passive"))
    )
    (net (code "196") (name "unconnected-(RN11-Pad1)") (class "Default")
      (node (ref "RN11") (pin "1") (pinfunction "1_1") (pintype "passive+no_connect"))
    )
    (net (code "197") (name "unconnected-(RN11-Pad2)") (class "Default")
      (node (ref "RN11") (pin "2") (pinfunction "2_2") (pintype "passive+no_connect"))
    )
    (net (code "198") (name "unconnected-(RN11-Pad7)") (class "Default")
      (node (ref "RN11") (pin "7") (pinfunction "7_7") (pintype "passive+no_connect"))
    )
    (net (code "199") (name "unconnected-(RN11-Pad8)") (class "Default")
      (node (ref "RN11") (pin "8") (pinfunction "8_8") (pintype "passive+no_connect"))
    )
    (net (code "200") (name "unconnected-(RN19-Pad3)") (class "Default")
      (node (ref "RN19") (pin "3") (pinfunction "3_3") (pintype "passive"))
    )
    (net (code "201") (name "unconnected-(RN19-Pad4)") (class "Default")
      (node (ref "RN19") (pin "4") (pinfunction "4_4") (pintype "passive"))
    )
    (net (code "202") (name "unconnected-(RN19-Pad5)") (class "Default")
      (node (ref "RN19") (pin "5") (pinfunction "5_5") (pintype "passive"))
    )
    (net (code "203") (name "unconnected-(RN19-Pad6)") (class "Default")
      (node (ref "RN19") (pin "6") (pinfunction "6_6") (pintype "passive"))
    )
  )
)
